# doan.net
KiCad netlist of a schematic drawn in EAGLE
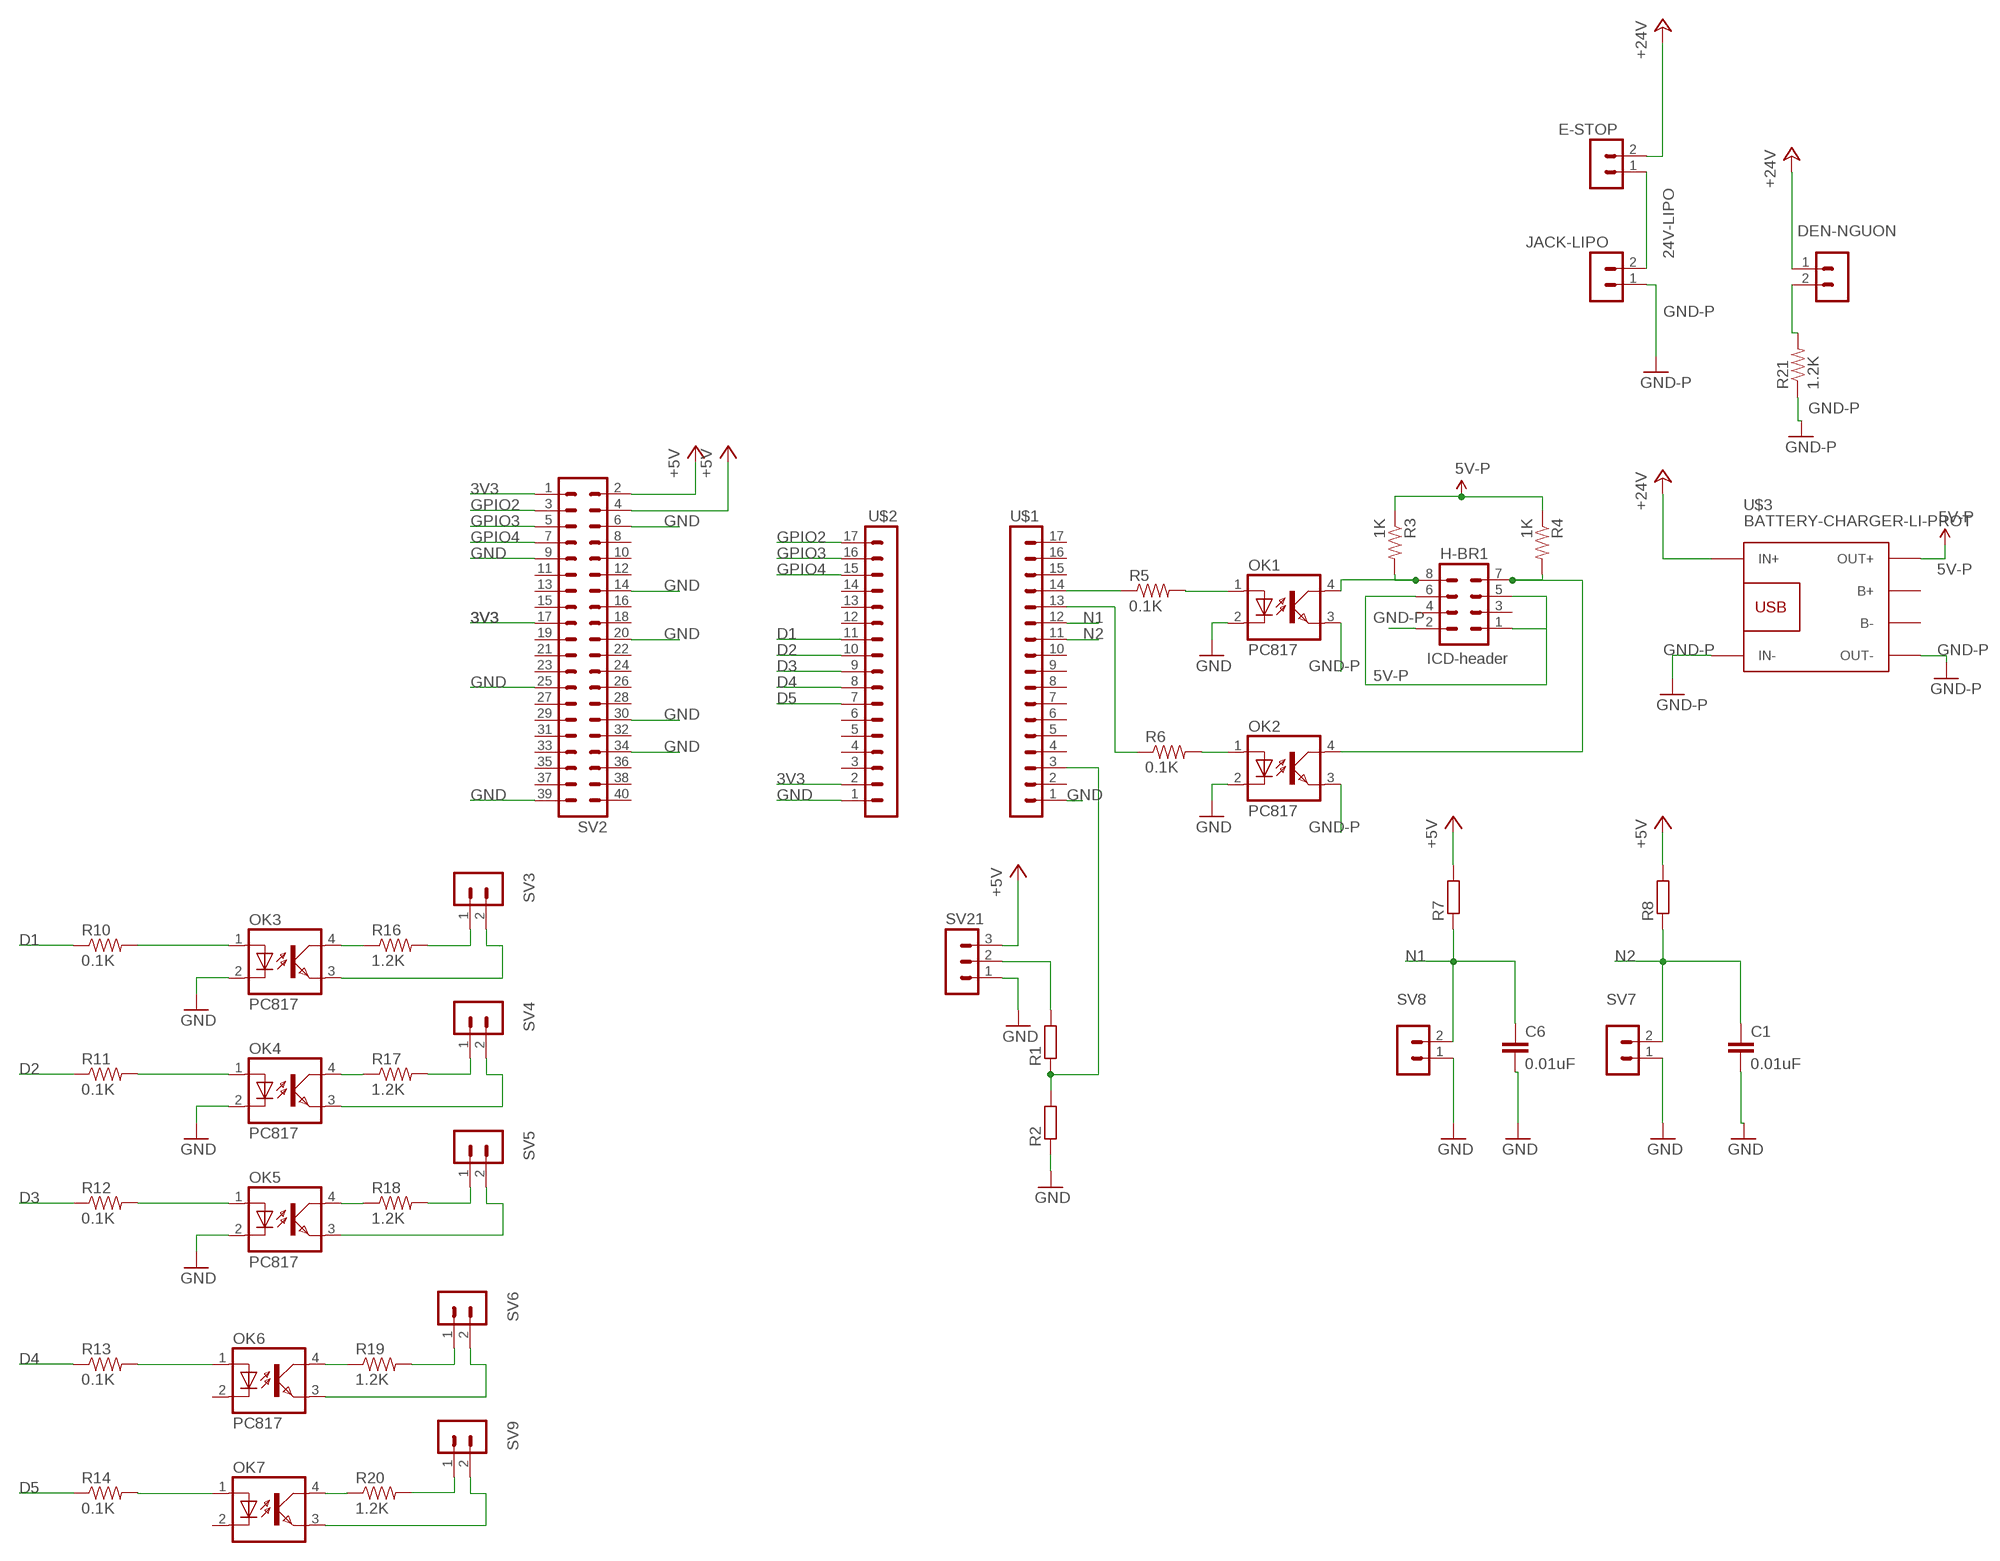
[diagram p0: schematic, sheet 1]

(export (version "E")
  (design (tool "Eeschema 10.0.6"))
  (components
    (comp (ref "C1")
      (value "0.01uF")
      (footprint "eagle-import:0805-CAP")
      (libsource (lib "eagle-import") (part "10UF10V10%(0805)"))
    )
    (comp (ref "C6")
      (value "0.01uF")
      (footprint "eagle-import:0805-CAP")
      (libsource (lib "eagle-import") (part "10UF10V10%(0805)"))
    )
    (comp (ref "DEN-NGUON")
      (value "MA02-1")
      (footprint "eagle-import:MA02-1")
      (libsource (lib "eagle-import") (part "MA02-1"))
    )
    (comp (ref "E-STOP")
      (value "MA02-1")
      (footprint "eagle-import:MA02-1")
      (libsource (lib "eagle-import") (part "MA02-1"))
    )
    (comp (ref "H-BR1")
      (value "MA04-2")
      (footprint "eagle-import:MA04-2")
      (libsource (lib "eagle-import") (part "MA04-2"))
    )
    (comp (ref "JACK-LIPO")
      (value "MA02-1")
      (footprint "eagle-import:MA02-1")
      (libsource (lib "eagle-import") (part "MA02-1"))
    )
    (comp (ref "OK1")
      (value "PC817")
      (footprint "eagle-import:DIL04")
      (fields (field (name "MPN") "PC817X4J000F"))
      (libsource (lib "eagle-import") (part "PC817"))
    )
    (comp (ref "OK2")
      (value "PC817")
      (footprint "eagle-import:DIL04")
      (fields (field (name "MPN") "PC817X4J000F"))
      (libsource (lib "eagle-import") (part "PC817"))
    )
    (comp (ref "OK3")
      (value "PC817")
      (footprint "eagle-import:DIL04")
      (fields (field (name "MPN") "PC817X4J000F"))
      (libsource (lib "eagle-import") (part "PC817"))
    )
    (comp (ref "OK4")
      (value "PC817")
      (footprint "eagle-import:DIL04")
      (fields (field (name "MPN") "PC817X4J000F"))
      (libsource (lib "eagle-import") (part "PC817"))
    )
    (comp (ref "OK5")
      (value "PC817")
      (footprint "eagle-import:DIL04")
      (fields (field (name "MPN") "PC817X4J000F"))
      (libsource (lib "eagle-import") (part "PC817"))
    )
    (comp (ref "OK6")
      (value "PC817")
      (footprint "eagle-import:DIL04")
      (fields (field (name "MPN") "PC817X4J000F"))
      (libsource (lib "eagle-import") (part "PC817"))
    )
    (comp (ref "OK7")
      (value "PC817")
      (footprint "eagle-import:DIL04")
      (fields (field (name "MPN") "PC817X4J000F"))
      (libsource (lib "eagle-import") (part "PC817"))
    )
    (comp (ref "R1")
      (value "R-EU_0309/10")
      (footprint "eagle-import:0309_10")
      (libsource (lib "eagle-import") (part "R-EU_0309/10"))
    )
    (comp (ref "R2")
      (value "R-EU_0309/10")
      (footprint "eagle-import:0309_10")
      (libsource (lib "eagle-import") (part "R-EU_0309/10"))
    )
    (comp (ref "R3")
      (value "1K")
      (footprint "eagle-import:0805")
      (libsource (lib "eagle-import") (part "0.3OHM-1/8W-1%(0805)"))
    )
    (comp (ref "R4")
      (value "1K")
      (footprint "eagle-import:0805")
      (libsource (lib "eagle-import") (part "0.3OHM-1/8W-1%(0805)"))
    )
    (comp (ref "R5")
      (value "0.1K")
      (footprint "eagle-import:0805")
      (libsource (lib "eagle-import") (part "0.3OHM-1/8W-1%(0805)"))
    )
    (comp (ref "R6")
      (value "0.1K")
      (footprint "eagle-import:0805")
      (libsource (lib "eagle-import") (part "0.3OHM-1/8W-1%(0805)"))
    )
    (comp (ref "R7")
      (value "R-EU_0309/10")
      (footprint "eagle-import:0309_10")
      (libsource (lib "eagle-import") (part "R-EU_0309/10"))
    )
    (comp (ref "R8")
      (value "R-EU_0309/10")
      (footprint "eagle-import:0309_10")
      (libsource (lib "eagle-import") (part "R-EU_0309/10"))
    )
    (comp (ref "R10")
      (value "0.1K")
      (footprint "eagle-import:0805")
      (libsource (lib "eagle-import") (part "0.3OHM-1/8W-1%(0805)"))
    )
    (comp (ref "R11")
      (value "0.1K")
      (footprint "eagle-import:0805")
      (libsource (lib "eagle-import") (part "0.3OHM-1/8W-1%(0805)"))
    )
    (comp (ref "R12")
      (value "0.1K")
      (footprint "eagle-import:0805")
      (libsource (lib "eagle-import") (part "0.3OHM-1/8W-1%(0805)"))
    )
    (comp (ref "R13")
      (value "0.1K")
      (footprint "eagle-import:0805")
      (libsource (lib "eagle-import") (part "0.3OHM-1/8W-1%(0805)"))
    )
    (comp (ref "R14")
      (value "0.1K")
      (footprint "eagle-import:0805")
      (libsource (lib "eagle-import") (part "0.3OHM-1/8W-1%(0805)"))
    )
    (comp (ref "R16")
      (value "1.2K")
      (footprint "eagle-import:0805")
      (libsource (lib "eagle-import") (part "0.3OHM-1/8W-1%(0805)"))
    )
    (comp (ref "R17")
      (value "1.2K")
      (footprint "eagle-import:0805")
      (libsource (lib "eagle-import") (part "0.3OHM-1/8W-1%(0805)"))
    )
    (comp (ref "R18")
      (value "1.2K")
      (footprint "eagle-import:0805")
      (libsource (lib "eagle-import") (part "0.3OHM-1/8W-1%(0805)"))
    )
    (comp (ref "R19")
      (value "1.2K")
      (footprint "eagle-import:0805")
      (libsource (lib "eagle-import") (part "0.3OHM-1/8W-1%(0805)"))
    )
    (comp (ref "R20")
      (value "1.2K")
      (footprint "eagle-import:0805")
      (libsource (lib "eagle-import") (part "0.3OHM-1/8W-1%(0805)"))
    )
    (comp (ref "R21")
      (value "1.2K")
      (footprint "eagle-import:0805")
      (libsource (lib "eagle-import") (part "0.3OHM-1/8W-1%(0805)"))
    )
    (comp (ref "SV2")
      (value "MA20-2W")
      (footprint "eagle-import:MA20-2W")
      (libsource (lib "eagle-import") (part "MA20-2W"))
    )
    (comp (ref "SV3")
      (value "MA02-1")
      (footprint "eagle-import:MA02-1")
      (libsource (lib "eagle-import") (part "MA02-1"))
    )
    (comp (ref "SV4")
      (value "MA02-1")
      (footprint "eagle-import:MA02-1")
      (libsource (lib "eagle-import") (part "MA02-1"))
    )
    (comp (ref "SV5")
      (value "MA02-1")
      (footprint "eagle-import:MA02-1")
      (libsource (lib "eagle-import") (part "MA02-1"))
    )
    (comp (ref "SV6")
      (value "MA02-1")
      (footprint "eagle-import:MA02-1")
      (libsource (lib "eagle-import") (part "MA02-1"))
    )
    (comp (ref "SV7")
      (value "MA02-1")
      (footprint "eagle-import:MA02-1")
      (libsource (lib "eagle-import") (part "MA02-1"))
    )
    (comp (ref "SV8")
      (value "MA02-1")
      (footprint "eagle-import:MA02-1")
      (libsource (lib "eagle-import") (part "MA02-1"))
    )
    (comp (ref "SV9")
      (value "MA02-1")
      (footprint "eagle-import:MA02-1")
      (libsource (lib "eagle-import") (part "MA02-1"))
    )
    (comp (ref "SV21")
      (value "MA03-1")
      (footprint "eagle-import:MA03-1")
      (libsource (lib "eagle-import") (part "MA03-1"))
    )
    (comp (ref "U$1")
      (value "MA17-1")
      (footprint "eagle-import:MA17-1")
      (libsource (lib "eagle-import") (part "MA17-1"))
    )
    (comp (ref "U$2")
      (value "MA17-1")
      (footprint "eagle-import:MA17-1")
      (libsource (lib "eagle-import") (part "MA17-1"))
    )
    (comp (ref "U$3")
      (value "BATTERY-CHARGER-LI-PROT")
      (footprint "eagle-import:BATTERY-CHARGER-LI-PROT")
      (libsource (lib "eagle-import") (part "BATTERY-CHARGER-LI-PROT"))
    )
  )
  (nets
    (net (code "1") (name "+5V") (class "Default")
      (node (ref "R7") (pin "2") (pinfunction "2_2") (pintype "passive"))
      (node (ref "R8") (pin "2") (pinfunction "2_2") (pintype "passive"))
      (node (ref "SV2") (pin "2") (pinfunction "2_2") (pintype "passive"))
      (node (ref "SV2") (pin "4") (pinfunction "4_4") (pintype "passive"))
      (node (ref "SV21") (pin "3") (pinfunction "3_3") (pintype "passive"))
    )
    (net (code "2") (name "+24V") (class "Default")
      (node (ref "DEN-NGUON") (pin "1") (pinfunction "1_1") (pintype "passive"))
      (node (ref "E-STOP") (pin "2") (pinfunction "2_2") (pintype "passive"))
      (node (ref "U$3") (pin "IN+") (pinfunction "IN+_IN+") (pintype "bidirectional"))
    )
    (net (code "3") (name "/3V3") (class "Default")
      (node (ref "SV2") (pin "1") (pinfunction "1_1") (pintype "passive"))
      (node (ref "SV2") (pin "17") (pinfunction "17_17") (pintype "passive"))
      (node (ref "U$2") (pin "2") (pinfunction "2_2") (pintype "passive"))
    )
    (net (code "4") (name "/24V-LIPO") (class "Default")
      (node (ref "E-STOP") (pin "1") (pinfunction "1_1") (pintype "passive"))
      (node (ref "JACK-LIPO") (pin "2") (pinfunction "2_2") (pintype "passive"))
    )
    (net (code "5") (name "/D1") (class "Default")
      (node (ref "R10") (pin "1") (pinfunction "1_1") (pintype "passive"))
      (node (ref "U$2") (pin "11") (pinfunction "11_11") (pintype "passive"))
    )
    (net (code "6") (name "/D2") (class "Default")
      (node (ref "R11") (pin "1") (pinfunction "1_1") (pintype "passive"))
      (node (ref "U$2") (pin "10") (pinfunction "10_10") (pintype "passive"))
    )
    (net (code "7") (name "/D3") (class "Default")
      (node (ref "R12") (pin "1") (pinfunction "1_1") (pintype "passive"))
      (node (ref "U$2") (pin "9") (pinfunction "9_9") (pintype "passive"))
    )
    (net (code "8") (name "/D4") (class "Default")
      (node (ref "R13") (pin "1") (pinfunction "1_1") (pintype "passive"))
      (node (ref "U$2") (pin "8") (pinfunction "8_8") (pintype "passive"))
    )
    (net (code "9") (name "/D5") (class "Default")
      (node (ref "R14") (pin "1") (pinfunction "1_1") (pintype "passive"))
      (node (ref "U$2") (pin "7") (pinfunction "7_7") (pintype "passive"))
    )
    (net (code "10") (name "/GPIO2") (class "Default")
      (node (ref "SV2") (pin "3") (pinfunction "3_3") (pintype "passive"))
      (node (ref "U$2") (pin "17") (pinfunction "17_17") (pintype "passive"))
    )
    (net (code "11") (name "/GPIO3") (class "Default")
      (node (ref "SV2") (pin "5") (pinfunction "5_5") (pintype "passive"))
      (node (ref "U$2") (pin "16") (pinfunction "16_16") (pintype "passive"))
    )
    (net (code "12") (name "/GPIO4") (class "Default")
      (node (ref "SV2") (pin "7") (pinfunction "7_7") (pintype "passive"))
      (node (ref "U$2") (pin "15") (pinfunction "15_15") (pintype "passive"))
    )
    (net (code "13") (name "/N1") (class "Default")
      (node (ref "C6") (pin "1") (pinfunction "1_1") (pintype "passive"))
      (node (ref "R7") (pin "1") (pinfunction "1_1") (pintype "passive"))
      (node (ref "SV8") (pin "2") (pinfunction "2_2") (pintype "passive"))
      (node (ref "U$1") (pin "12") (pinfunction "12_12") (pintype "passive"))
    )
    (net (code "14") (name "/N2") (class "Default")
      (node (ref "C1") (pin "1") (pinfunction "1_1") (pintype "passive"))
      (node (ref "R8") (pin "1") (pinfunction "1_1") (pintype "passive"))
      (node (ref "SV7") (pin "2") (pinfunction "2_2") (pintype "passive"))
      (node (ref "U$1") (pin "11") (pinfunction "11_11") (pintype "passive"))
    )
    (net (code "15") (name "5V-P") (class "Default")
      (node (ref "H-BR1") (pin "1") (pinfunction "1_1") (pintype "passive"))
      (node (ref "H-BR1") (pin "5") (pinfunction "5_5") (pintype "passive"))
      (node (ref "H-BR1") (pin "6") (pinfunction "6_6") (pintype "passive"))
      (node (ref "R3") (pin "1") (pinfunction "1_1") (pintype "passive"))
      (node (ref "R4") (pin "1") (pinfunction "1_1") (pintype "passive"))
      (node (ref "U$3") (pin "OUT+") (pinfunction "OUT+_OUT+") (pintype "bidirectional"))
    )
    (net (code "16") (name "GND") (class "Default")
      (node (ref "C1") (pin "2") (pinfunction "2_2") (pintype "passive"))
      (node (ref "C6") (pin "2") (pinfunction "2_2") (pintype "passive"))
      (node (ref "OK1") (pin "2") (pinfunction "C_2") (pintype "passive"))
      (node (ref "OK2") (pin "2") (pinfunction "C_2") (pintype "passive"))
      (node (ref "OK3") (pin "2") (pinfunction "C_2") (pintype "passive"))
      (node (ref "OK4") (pin "2") (pinfunction "C_2") (pintype "passive"))
      (node (ref "OK5") (pin "2") (pinfunction "C_2") (pintype "passive"))
      (node (ref "R2") (pin "1") (pinfunction "1_1") (pintype "passive"))
      (node (ref "SV2") (pin "14") (pinfunction "14_14") (pintype "passive"))
      (node (ref "SV2") (pin "20") (pinfunction "20_20") (pintype "passive"))
      (node (ref "SV2") (pin "25") (pinfunction "25_25") (pintype "passive"))
      (node (ref "SV2") (pin "30") (pinfunction "30_30") (pintype "passive"))
      (node (ref "SV2") (pin "34") (pinfunction "34_34") (pintype "passive"))
      (node (ref "SV2") (pin "39") (pinfunction "39_39") (pintype "passive"))
      (node (ref "SV2") (pin "6") (pinfunction "6_6") (pintype "passive"))
      (node (ref "SV2") (pin "9") (pinfunction "9_9") (pintype "passive"))
      (node (ref "SV21") (pin "1") (pinfunction "1_1") (pintype "passive"))
      (node (ref "SV7") (pin "1") (pinfunction "1_1") (pintype "passive"))
      (node (ref "SV8") (pin "1") (pinfunction "1_1") (pintype "passive"))
      (node (ref "U$1") (pin "1") (pinfunction "1_1") (pintype "passive"))
      (node (ref "U$2") (pin "1") (pinfunction "1_1") (pintype "passive"))
    )
    (net (code "17") (name "GND-P") (class "Default")
      (node (ref "H-BR1") (pin "2") (pinfunction "2_2") (pintype "passive"))
      (node (ref "JACK-LIPO") (pin "1") (pinfunction "1_1") (pintype "passive"))
      (node (ref "OK1") (pin "3") (pinfunction "EMIT_3") (pintype "passive"))
      (node (ref "OK2") (pin "3") (pinfunction "EMIT_3") (pintype "passive"))
      (node (ref "R21") (pin "1") (pinfunction "1_1") (pintype "passive"))
      (node (ref "U$3") (pin "IN-") (pinfunction "IN-_IN-") (pintype "bidirectional"))
      (node (ref "U$3") (pin "OUT-") (pinfunction "OUT-_OUT-") (pintype "bidirectional"))
    )
    (net (code "18") (name "Net-(OK1-A)") (class "Default")
      (node (ref "OK1") (pin "1") (pinfunction "A_1") (pintype "passive"))
      (node (ref "R5") (pin "2") (pinfunction "2_2") (pintype "passive"))
    )
    (net (code "19") (name "Net-(OK1-COL)") (class "Default")
      (node (ref "H-BR1") (pin "8") (pinfunction "8_8") (pintype "passive"))
      (node (ref "OK1") (pin "4") (pinfunction "COL_4") (pintype "passive"))
      (node (ref "R3") (pin "2") (pinfunction "2_2") (pintype "passive"))
    )
    (net (code "20") (name "Net-(OK2-A)") (class "Default")
      (node (ref "OK2") (pin "1") (pinfunction "A_1") (pintype "passive"))
      (node (ref "R6") (pin "2") (pinfunction "2_2") (pintype "passive"))
    )
    (net (code "21") (name "Net-(OK2-COL)") (class "Default")
      (node (ref "H-BR1") (pin "7") (pinfunction "7_7") (pintype "passive"))
      (node (ref "OK2") (pin "4") (pinfunction "COL_4") (pintype "passive"))
      (node (ref "R4") (pin "2") (pinfunction "2_2") (pintype "passive"))
    )
    (net (code "22") (name "Net-(OK3-A)") (class "Default")
      (node (ref "OK3") (pin "1") (pinfunction "A_1") (pintype "passive"))
      (node (ref "R10") (pin "2") (pinfunction "2_2") (pintype "passive"))
    )
    (net (code "23") (name "Net-(OK3-COL)") (class "Default")
      (node (ref "OK3") (pin "4") (pinfunction "COL_4") (pintype "passive"))
      (node (ref "R16") (pin "1") (pinfunction "1_1") (pintype "passive"))
    )
    (net (code "24") (name "Net-(OK3-EMIT)") (class "Default")
      (node (ref "OK3") (pin "3") (pinfunction "EMIT_3") (pintype "passive"))
      (node (ref "SV3") (pin "2") (pinfunction "2_2") (pintype "passive"))
    )
    (net (code "25") (name "Net-(OK4-A)") (class "Default")
      (node (ref "OK4") (pin "1") (pinfunction "A_1") (pintype "passive"))
      (node (ref "R11") (pin "2") (pinfunction "2_2") (pintype "passive"))
    )
    (net (code "26") (name "Net-(OK4-COL)") (class "Default")
      (node (ref "OK4") (pin "4") (pinfunction "COL_4") (pintype "passive"))
      (node (ref "R17") (pin "1") (pinfunction "1_1") (pintype "passive"))
    )
    (net (code "27") (name "Net-(OK4-EMIT)") (class "Default")
      (node (ref "OK4") (pin "3") (pinfunction "EMIT_3") (pintype "passive"))
      (node (ref "SV4") (pin "2") (pinfunction "2_2") (pintype "passive"))
    )
    (net (code "28") (name "Net-(OK5-A)") (class "Default")
      (node (ref "OK5") (pin "1") (pinfunction "A_1") (pintype "passive"))
      (node (ref "R12") (pin "2") (pinfunction "2_2") (pintype "passive"))
    )
    (net (code "29") (name "Net-(OK5-COL)") (class "Default")
      (node (ref "OK5") (pin "4") (pinfunction "COL_4") (pintype "passive"))
      (node (ref "R18") (pin "1") (pinfunction "1_1") (pintype "passive"))
    )
    (net (code "30") (name "Net-(OK5-EMIT)") (class "Default")
      (node (ref "OK5") (pin "3") (pinfunction "EMIT_3") (pintype "passive"))
      (node (ref "SV5") (pin "2") (pinfunction "2_2") (pintype "passive"))
    )
    (net (code "31") (name "Net-(OK6-A)") (class "Default")
      (node (ref "OK6") (pin "1") (pinfunction "A_1") (pintype "passive"))
      (node (ref "R13") (pin "2") (pinfunction "2_2") (pintype "passive"))
    )
    (net (code "32") (name "Net-(OK6-COL)") (class "Default")
      (node (ref "OK6") (pin "4") (pinfunction "COL_4") (pintype "passive"))
      (node (ref "R19") (pin "1") (pinfunction "1_1") (pintype "passive"))
    )
    (net (code "33") (name "Net-(OK6-EMIT)") (class "Default")
      (node (ref "OK6") (pin "3") (pinfunction "EMIT_3") (pintype "passive"))
      (node (ref "SV6") (pin "2") (pinfunction "2_2") (pintype "passive"))
    )
    (net (code "34") (name "Net-(OK7-A)") (class "Default")
      (node (ref "OK7") (pin "1") (pinfunction "A_1") (pintype "passive"))
      (node (ref "R14") (pin "2") (pinfunction "2_2") (pintype "passive"))
    )
    (net (code "35") (name "Net-(OK7-COL)") (class "Default")
      (node (ref "OK7") (pin "4") (pinfunction "COL_4") (pintype "passive"))
      (node (ref "R20") (pin "1") (pinfunction "1_1") (pintype "passive"))
    )
    (net (code "36") (name "Net-(OK7-EMIT)") (class "Default")
      (node (ref "OK7") (pin "3") (pinfunction "EMIT_3") (pintype "passive"))
      (node (ref "SV9") (pin "2") (pinfunction "2_2") (pintype "passive"))
    )
    (net (code "37") (name "Net-(R1-Pad1)") (class "Default")
      (node (ref "R1") (pin "1") (pinfunction "1_1") (pintype "passive"))
      (node (ref "R2") (pin "2") (pinfunction "2_2") (pintype "passive"))
      (node (ref "U$1") (pin "3") (pinfunction "3_3") (pintype "passive"))
    )
    (net (code "38") (name "Net-(R1-Pad2)") (class "Default")
      (node (ref "R1") (pin "2") (pinfunction "2_2") (pintype "passive"))
      (node (ref "SV21") (pin "2") (pinfunction "2_2") (pintype "passive"))
    )
    (net (code "39") (name "Net-(R5-Pad1)") (class "Default")
      (node (ref "R5") (pin "1") (pinfunction "1_1") (pintype "passive"))
      (node (ref "U$1") (pin "14") (pinfunction "14_14") (pintype "passive"))
    )
    (net (code "40") (name "Net-(R6-Pad1)") (class "Default")
      (node (ref "R6") (pin "1") (pinfunction "1_1") (pintype "passive"))
      (node (ref "U$1") (pin "13") (pinfunction "13_13") (pintype "passive"))
    )
    (net (code "41") (name "Net-(R16-Pad2)") (class "Default")
      (node (ref "R16") (pin "2") (pinfunction "2_2") (pintype "passive"))
      (node (ref "SV3") (pin "1") (pinfunction "1_1") (pintype "passive"))
    )
    (net (code "42") (name "Net-(R17-Pad2)") (class "Default")
      (node (ref "R17") (pin "2") (pinfunction "2_2") (pintype "passive"))
      (node (ref "SV4") (pin "1") (pinfunction "1_1") (pintype "passive"))
    )
    (net (code "43") (name "Net-(R18-Pad2)") (class "Default")
      (node (ref "R18") (pin "2") (pinfunction "2_2") (pintype "passive"))
      (node (ref "SV5") (pin "1") (pinfunction "1_1") (pintype "passive"))
    )
    (net (code "44") (name "Net-(R19-Pad2)") (class "Default")
      (node (ref "R19") (pin "2") (pinfunction "2_2") (pintype "passive"))
      (node (ref "SV6") (pin "1") (pinfunction "1_1") (pintype "passive"))
    )
    (net (code "45") (name "Net-(R20-Pad2)") (class "Default")
      (node (ref "R20") (pin "2") (pinfunction "2_2") (pintype "passive"))
      (node (ref "SV9") (pin "1") (pinfunction "1_1") (pintype "passive"))
    )
    (net (code "46") (name "unconnected-(DEN-NGUON-Pad2)") (class "Default")
      (node (ref "DEN-NGUON") (pin "2") (pinfunction "2_2") (pintype "passive"))
    )
    (net (code "47") (name "unconnected-(H-BR1-Pad3)") (class "Default")
      (node (ref "H-BR1") (pin "3") (pinfunction "3_3") (pintype "passive"))
    )
    (net (code "48") (name "unconnected-(H-BR1-Pad4)") (class "Default")
      (node (ref "H-BR1") (pin "4") (pinfunction "4_4") (pintype "passive"))
    )
    (net (code "49") (name "unconnected-(OK6-C-Pad2)") (class "Default")
      (node (ref "OK6") (pin "2") (pinfunction "C_2") (pintype "passive"))
    )
    (net (code "50") (name "unconnected-(OK7-C-Pad2)") (class "Default")
      (node (ref "OK7") (pin "2") (pinfunction "C_2") (pintype "passive"))
    )
    (net (code "51") (name "unconnected-(R21-Pad2)") (class "Default")
      (node (ref "R21") (pin "2") (pinfunction "2_2") (pintype "passive"))
    )
    (net (code "52") (name "unconnected-(SV2-Pad8)") (class "Default")
      (node (ref "SV2") (pin "8") (pinfunction "8_8") (pintype "passive"))
    )
    (net (code "53") (name "unconnected-(SV2-Pad10)") (class "Default")
      (node (ref "SV2") (pin "10") (pinfunction "10_10") (pintype "passive"))
    )
    (net (code "54") (name "unconnected-(SV2-Pad11)") (class "Default")
      (node (ref "SV2") (pin "11") (pinfunction "11_11") (pintype "passive"))
    )
    (net (code "55") (name "unconnected-(SV2-Pad12)") (class "Default")
      (node (ref "SV2") (pin "12") (pinfunction "12_12") (pintype "passive"))
    )
    (net (code "56") (name "unconnected-(SV2-Pad13)") (class "Default")
      (node (ref "SV2") (pin "13") (pinfunction "13_13") (pintype "passive"))
    )
    (net (code "57") (name "unconnected-(SV2-Pad15)") (class "Default")
      (node (ref "SV2") (pin "15") (pinfunction "15_15") (pintype "passive"))
    )
    (net (code "58") (name "unconnected-(SV2-Pad16)") (class "Default")
      (node (ref "SV2") (pin "16") (pinfunction "16_16") (pintype "passive"))
    )
    (net (code "59") (name "unconnected-(SV2-Pad18)") (class "Default")
      (node (ref "SV2") (pin "18") (pinfunction "18_18") (pintype "passive"))
    )
    (net (code "60") (name "unconnected-(SV2-Pad19)") (class "Default")
      (node (ref "SV2") (pin "19") (pinfunction "19_19") (pintype "passive"))
    )
    (net (code "61") (name "unconnected-(SV2-Pad21)") (class "Default")
      (node (ref "SV2") (pin "21") (pinfunction "21_21") (pintype "passive"))
    )
    (net (code "62") (name "unconnected-(SV2-Pad22)") (class "Default")
      (node (ref "SV2") (pin "22") (pinfunction "22_22") (pintype "passive"))
    )
    (net (code "63") (name "unconnected-(SV2-Pad23)") (class "Default")
      (node (ref "SV2") (pin "23") (pinfunction "23_23") (pintype "passive"))
    )
    (net (code "64") (name "unconnected-(SV2-Pad24)") (class "Default")
      (node (ref "SV2") (pin "24") (pinfunction "24_24") (pintype "passive"))
    )
    (net (code "65") (name "unconnected-(SV2-Pad26)") (class "Default")
      (node (ref "SV2") (pin "26") (pinfunction "26_26") (pintype "passive"))
    )
    (net (code "66") (name "unconnected-(SV2-Pad27)") (class "Default")
      (node (ref "SV2") (pin "27") (pinfunction "27_27") (pintype "passive"))
    )
    (net (code "67") (name "unconnected-(SV2-Pad28)") (class "Default")
      (node (ref "SV2") (pin "28") (pinfunction "28_28") (pintype "passive"))
    )
    (net (code "68") (name "unconnected-(SV2-Pad29)") (class "Default")
      (node (ref "SV2") (pin "29") (pinfunction "29_29") (pintype "passive"))
    )
    (net (code "69") (name "unconnected-(SV2-Pad31)") (class "Default")
      (node (ref "SV2") (pin "31") (pinfunction "31_31") (pintype "passive"))
    )
    (net (code "70") (name "unconnected-(SV2-Pad32)") (class "Default")
      (node (ref "SV2") (pin "32") (pinfunction "32_32") (pintype "passive"))
    )
    (net (code "71") (name "unconnected-(SV2-Pad33)") (class "Default")
      (node (ref "SV2") (pin "33") (pinfunction "33_33") (pintype "passive"))
    )
    (net (code "72") (name "unconnected-(SV2-Pad35)") (class "Default")
      (node (ref "SV2") (pin "35") (pinfunction "35_35") (pintype "passive"))
    )
    (net (code "73") (name "unconnected-(SV2-Pad36)") (class "Default")
      (node (ref "SV2") (pin "36") (pinfunction "36_36") (pintype "passive"))
    )
    (net (code "74") (name "unconnected-(SV2-Pad37)") (class "Default")
      (node (ref "SV2") (pin "37") (pinfunction "37_37") (pintype "passive"))
    )
    (net (code "75") (name "unconnected-(SV2-Pad38)") (class "Default")
      (node (ref "SV2") (pin "38") (pinfunction "38_38") (pintype "passive"))
    )
    (net (code "76") (name "unconnected-(SV2-Pad40)") (class "Default")
      (node (ref "SV2") (pin "40") (pinfunction "40_40") (pintype "passive"))
    )
    (net (code "77") (name "unconnected-(U$1-Pad2)") (class "Default")
      (node (ref "U$1") (pin "2") (pinfunction "2_2") (pintype "passive"))
    )
    (net (code "78") (name "unconnected-(U$1-Pad4)") (class "Default")
      (node (ref "U$1") (pin "4") (pinfunction "4_4") (pintype "passive"))
    )
    (net (code "79") (name "unconnected-(U$1-Pad5)") (class "Default")
      (node (ref "U$1") (pin "5") (pinfunction "5_5") (pintype "passive"))
    )
    (net (code "80") (name "unconnected-(U$1-Pad6)") (class "Default")
      (node (ref "U$1") (pin "6") (pinfunction "6_6") (pintype "passive"))
    )
    (net (code "81") (name "unconnected-(U$1-Pad7)") (class "Default")
      (node (ref "U$1") (pin "7") (pinfunction "7_7") (pintype "passive"))
    )
    (net (code "82") (name "unconnected-(U$1-Pad8)") (class "Default")
      (node (ref "U$1") (pin "8") (pinfunction "8_8") (pintype "passive"))
    )
    (net (code "83") (name "unconnected-(U$1-Pad9)") (class "Default")
      (node (ref "U$1") (pin "9") (pinfunction "9_9") (pintype "passive"))
    )
    (net (code "84") (name "unconnected-(U$1-Pad10)") (class "Default")
      (node (ref "U$1") (pin "10") (pinfunction "10_10") (pintype "passive"))
    )
    (net (code "85") (name "unconnected-(U$1-Pad15)") (class "Default")
      (node (ref "U$1") (pin "15") (pinfunction "15_15") (pintype "passive"))
    )
    (net (code "86") (name "unconnected-(U$1-Pad16)") (class "Default")
      (node (ref "U$1") (pin "16") (pinfunction "16_16") (pintype "passive"))
    )
    (net (code "87") (name "unconnected-(U$1-Pad17)") (class "Default")
      (node (ref "U$1") (pin "17") (pinfunction "17_17") (pintype "passive"))
    )
    (net (code "88") (name "unconnected-(U$2-Pad3)") (class "Default")
      (node (ref "U$2") (pin "3") (pinfunction "3_3") (pintype "passive"))
    )
    (net (code "89") (name "unconnected-(U$2-Pad4)") (class "Default")
      (node (ref "U$2") (pin "4") (pinfunction "4_4") (pintype "passive"))
    )
    (net (code "90") (name "unconnected-(U$2-Pad5)") (class "Default")
      (node (ref "U$2") (pin "5") (pinfunction "5_5") (pintype "passive"))
    )
    (net (code "91") (name "unconnected-(U$2-Pad6)") (class "Default")
      (node (ref "U$2") (pin "6") (pinfunction "6_6") (pintype "passive"))
    )
    (net (code "92") (name "unconnected-(U$2-Pad12)") (class "Default")
      (node (ref "U$2") (pin "12") (pinfunction "12_12") (pintype "passive"))
    )
    (net (code "93") (name "unconnected-(U$2-Pad13)") (class "Default")
      (node (ref "U$2") (pin "13") (pinfunction "13_13") (pintype "passive"))
    )
    (net (code "94") (name "unconnected-(U$2-Pad14)") (class "Default")
      (node (ref "U$2") (pin "14") (pinfunction "14_14") (pintype "passive"))
    )
    (net (code "95") (name "unconnected-(U$3-PadB+)") (class "Default")
      (node (ref "U$3") (pin "B+") (pinfunction "B+_B+") (pintype "bidirectional"))
    )
    (net (code "96") (name "unconnected-(U$3-PadB-)") (class "Default")
      (node (ref "U$3") (pin "B-") (pinfunction "B-_B-") (pintype "bidirectional"))
    )
  )
)
